# Sheet3_SenseCkts_Programming_Interface.net
KiCad netlist of a schematic drawn in Altium Designer
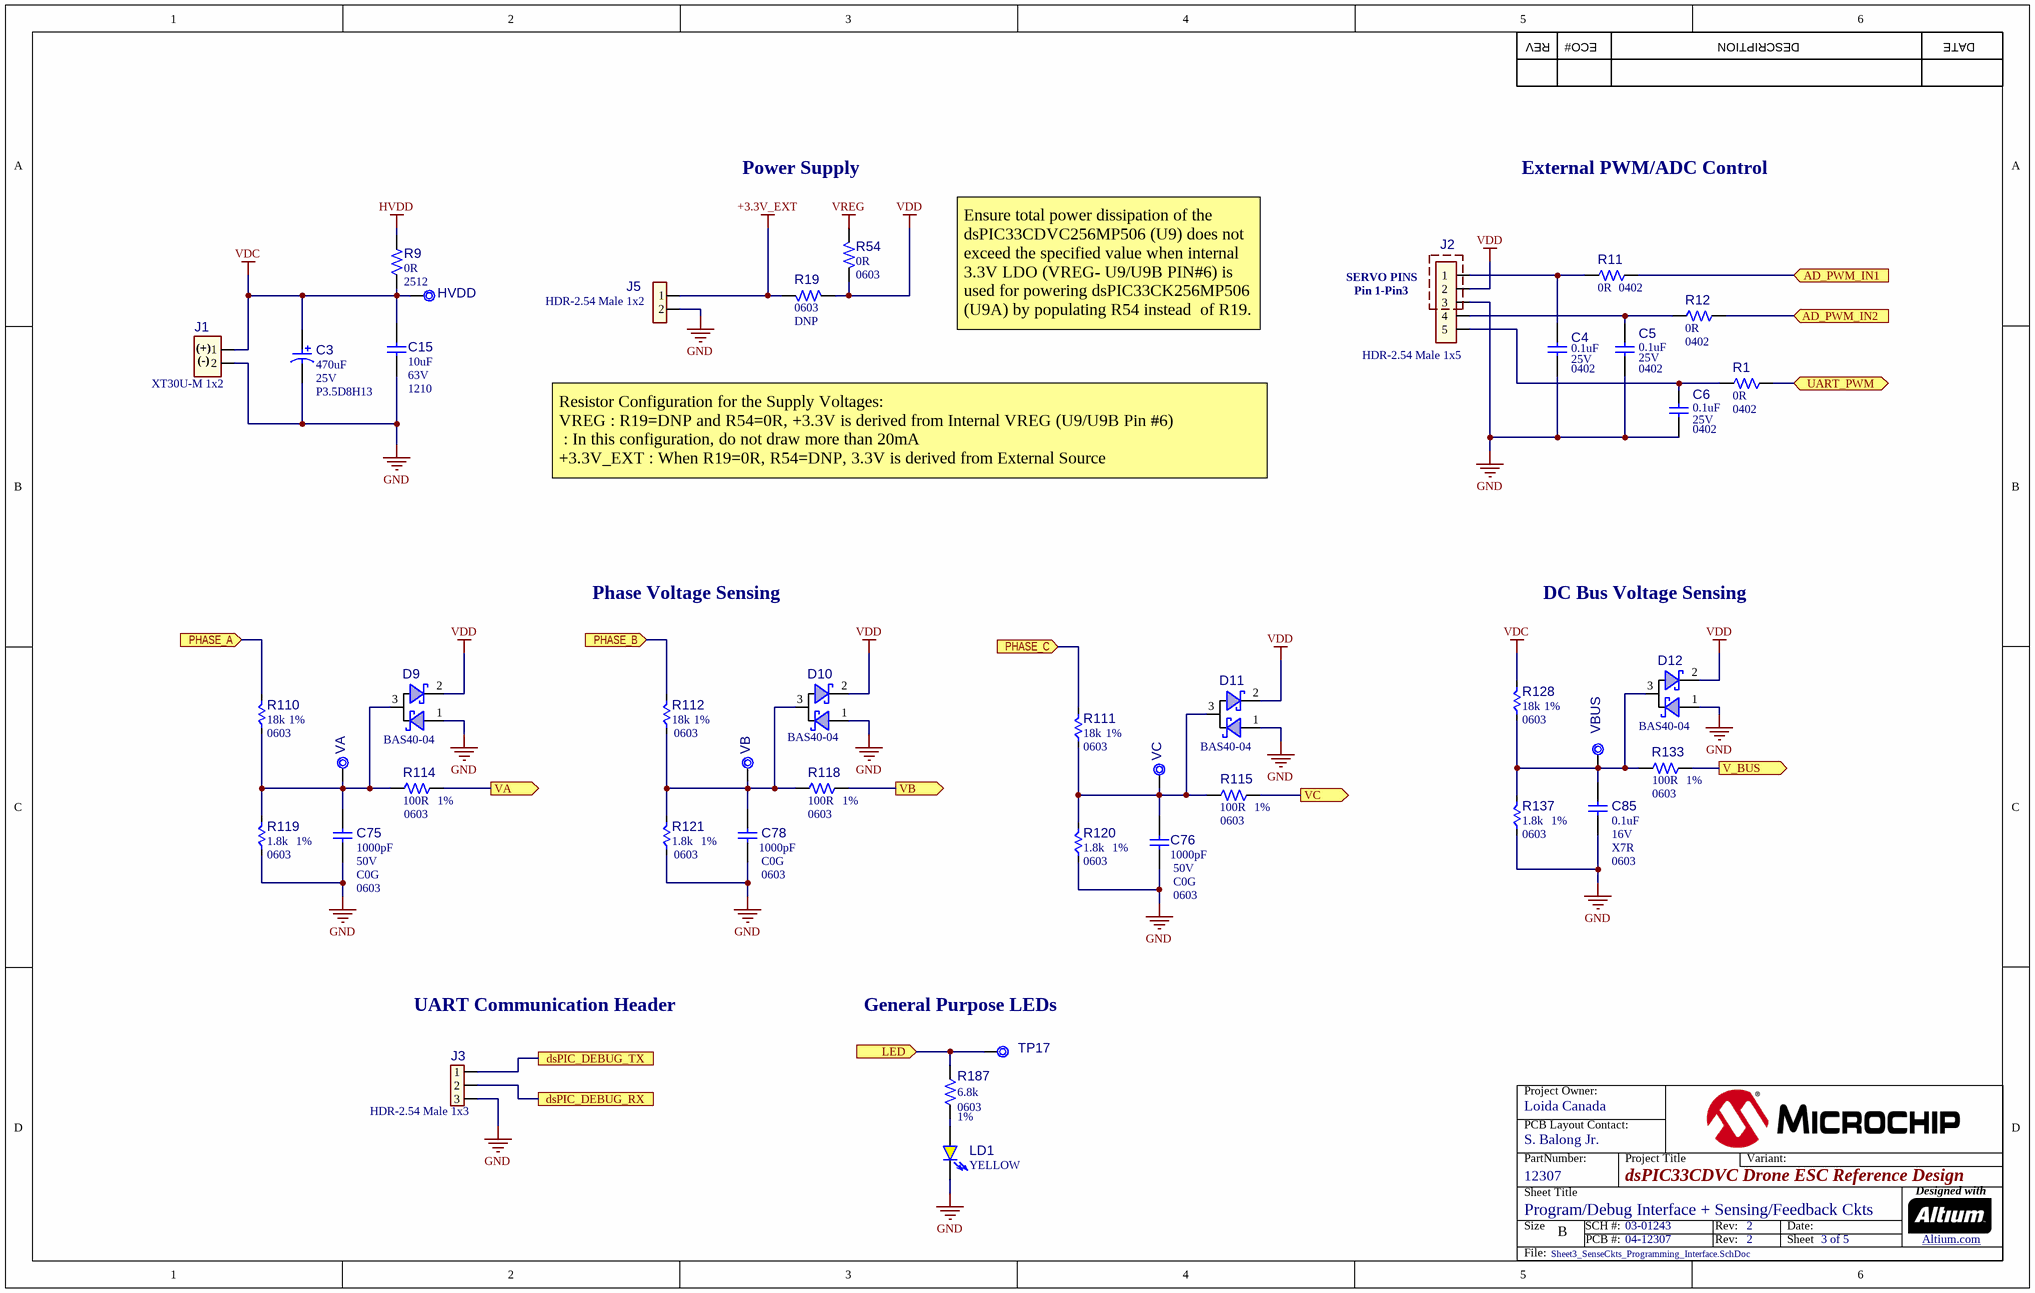
[diagram p0: Sheet3_SenseCkts_Programming_Interface.SchDoc]

(export (version "E")
  (design (tool "Eeschema 10.0.6"))
  (components
    (comp (ref "C3")
      (value "470uF")
      (footprint "CAP_RAD_P3.5D8H13_WE")
      (description "Capacitor")
      (fields
        (field (name "VOLTAGE") "25V")
        (field (name "PACKAGE") "P3.5D8H13")
        (field (name "TOLERANCE") "20%")
        (field (name "Comment") "Capacitor POL")
        (field (name "OWNER") "Severino Balong Jr.")
      )
      (libsource (lib "MCHP-CDB") (part "Capacitor POL"))
    )
    (comp (ref "C4")
      (value "0.1uF")
      (footprint "CAP_C_0402")
      (fields
        (field (name "VOLTAGE") "25V")
        (field (name "PACKAGE") "0402")
        (field (name "TOLERANCE") "10%")
        (field (name "Comment") "Capacitor NP")
        (field (name "OWNER") "Randolph Sobrepena")
      )
      (libsource (lib "") (part "Capacitor NP_1"))
    )
    (comp (ref "C5")
      (value "0.1uF")
      (footprint "CAP_C_0402")
      (fields
        (field (name "VOLTAGE") "25V")
        (field (name "PACKAGE") "0402")
        (field (name "TOLERANCE") "10%")
        (field (name "Comment") "Capacitor NP")
        (field (name "OWNER") "Randolph Sobrepena")
      )
      (libsource (lib "") (part "Capacitor NP_1"))
    )
    (comp (ref "C6")
      (value "0.1uF")
      (footprint "CAP_C_0402")
      (fields
        (field (name "VOLTAGE") "25V")
        (field (name "PACKAGE") "0402")
        (field (name "TOLERANCE") "10%")
        (field (name "Comment") "Capacitor NP")
        (field (name "OWNER") "Randolph Sobrepena")
      )
      (libsource (lib "") (part "Capacitor NP_1"))
    )
    (comp (ref "C15")
      (value "10uF")
      (footprint "CAP_C_1210")
      (fields
        (field (name "VOLTAGE") "63V")
        (field (name "PACKAGE") "1210")
        (field (name "TOLERANCE") "10%")
        (field (name "Comment") "Capacitor NP")
        (field (name "OWNER") "Narasimha Murthy")
      )
      (libsource (lib "") (part "Capacitor NP_1"))
    )
    (comp (ref "C75")
      (value "1000pF")
      (footprint "CAP_C_0603")
      (description "Capacitor")
      (fields
        (field (name "VOLTAGE") "50V")
        (field (name "PACKAGE") "0603")
        (field (name "TOLERANCE") "5%")
        (field (name "TEMPERATURE COEFFCIENT") "C0G")
        (field (name "Comment") "Capacitor NP")
      )
      (libsource (lib "MCHP-CDB") (part "Capacitor NP"))
    )
    (comp (ref "C76")
      (value "1000pF")
      (footprint "CAP_C_0603")
      (description "Capacitor")
      (fields
        (field (name "VOLTAGE") "50V")
        (field (name "PACKAGE") "0603")
        (field (name "TOLERANCE") "5%")
        (field (name "TEMPERATURE COEFFCIENT") "C0G")
        (field (name "Comment") "Capacitor NP")
      )
      (libsource (lib "MCHP-CDB") (part "Capacitor NP"))
    )
    (comp (ref "C78")
      (value "1000pF")
      (footprint "CAP_C_0603")
      (description "Capacitor")
      (fields
        (field (name "VOLTAGE") "50V")
        (field (name "PACKAGE") "0603")
        (field (name "TOLERANCE") "5%")
        (field (name "TEMPERATURE COEFFCIENT") "C0G")
      )
      (libsource (lib "MCHP-CDB") (part "Capacitor NP"))
    )
    (comp (ref "C85")
      (value "0.1uF")
      (footprint "CAP_C_0603")
      (description "Capacitor")
      (fields
        (field (name "VOLTAGE") "16V")
        (field (name "PACKAGE") "0603")
        (field (name "TOLERANCE") "10%")
        (field (name "TEMPERATURE COEFFCIENT") "X7R")
        (field (name "Comment") "Capacitor NP")
        (field (name "OWNER") "Cristian Papuc")
      )
      (libsource (lib "MCHP-CDB") (part "Capacitor NP"))
    )
    (comp (ref "D9")
      (value "BAS40-04")
      (footprint "SOT-23-3")
      (fields
        (field (name "POWER") "200mW")
        (field (name "Comment") "Diode Schottky Dual AK")
        (field (name "OWNER") "Stephen Humberd")
      )
      (libsource (lib "MCHP-CDB") (part "Diode Schottky Dual AK"))
    )
    (comp (ref "D10")
      (value "BAS40-04")
      (footprint "SOT-23-3")
      (fields
        (field (name "POWER") "200mW")
        (field (name "Comment") "Diode Schottky Dual AK")
        (field (name "OWNER") "Stephen Humberd")
      )
      (libsource (lib "MCHP-CDB") (part "Diode Schottky Dual AK"))
    )
    (comp (ref "D11")
      (value "BAS40-04")
      (footprint "SOT-23-3")
      (fields
        (field (name "POWER") "200mW")
        (field (name "Comment") "Diode Schottky Dual AK")
        (field (name "OWNER") "Stephen Humberd")
      )
      (libsource (lib "MCHP-CDB") (part "Diode Schottky Dual AK"))
    )
    (comp (ref "D12")
      (value "BAS40-04")
      (footprint "SOT-23-3")
      (fields
        (field (name "POWER") "200mW")
        (field (name "Comment") "Diode Schottky Dual AK")
        (field (name "OWNER") "Stephen Humberd")
      )
      (libsource (lib "MCHP-CDB") (part "Diode Schottky Dual AK"))
    )
    (comp (ref "HVDD")
      (value "Test Point No BOM")
      (footprint "TP_1.1x0.6")
      (description "Test Point")
      (fields (field (name "OWNER") "Severino Balong Jr."))
      (libsource (lib "MCHP-CDB") (part "Test Point No BOM"))
    )
    (comp (ref "J1")
      (value "XT30U-M 1x2")
      (footprint "CON TERMINAL XT30U-M 5mm 1x2 Male 30A TH V")
      (fields
        (field (name "VOLTAGE") "500V")
        (field (name "Comment") "CON 1x2 POLARIZED")
        (field (name "OWNER") "Octavian Stroe")
      )
      (libsource (lib "MCHP-CDB") (part "CON 1x2 POLARIZED"))
    )
    (comp (ref "J2")
      (value "HDR-2.54 Male 1x5")
      (footprint "HDR_M_2.54_1x5_MH5.84_IH2.54_TH3.2_TH_VERT")
      (fields (field (name "Comment") "Header 1x5") (field (name "OWNER") "Deepak Kariyappa"))
      (libsource (lib "MCHP-CDB") (part "Header 1x5"))
    )
    (comp (ref "J3")
      (value "HDR-2.54 Male 1x3")
      (footprint "HDR_M_2.54_1x3_TH_V_SAM_TSW-103-08-G-S")
      (fields
        (field (name "VOLTAGE") "550VAC")
        (field (name "Comment") "Header 1x3")
        (field (name "OWNER") "Dragos Danaila")
      )
      (libsource (lib "MCHP-CDB") (part "Header 1x3"))
    )
    (comp (ref "J5")
      (value "HDR-2.54 Male 1x2")
      (footprint "HDR_M_2.54_1x2_TH_V_SAM_TSW-102-08-G-S")
      (fields
        (field (name "VOLTAGE") "550VAC")
        (field (name "Comment") "Header 1x2")
        (field (name "OWNER") "Dragos Danaila")
      )
      (libsource (lib "MCHP-CDB") (part "Header 1x2"))
    )
    (comp (ref "LD1")
      (value "YELLOW")
      (footprint "LED_0603_Yellow")
      (description "LED")
      (fields
        (field (name "POWER") "72mW")
        (field (name "Comment") "LED_yellow")
        (field (name "OWNER") "Narasimha Murthy")
      )
      (libsource (lib "MCHP-CDB") (part "LED_yellow"))
    )
    (comp (ref "R1")
      (value "0R")
      (footprint "RES_C_0402")
      (description "Resistor")
      (fields
        (field (name "PACKAGE") "0402")
        (field (name "VOLTAGE") "50V")
        (field (name "POWER") "1/16W")
        (field (name "OWNER") "Balaji Narayana")
      )
      (libsource (lib "MCHP-CDB") (part "Resistor"))
    )
    (comp (ref "R9")
      (value "0R")
      (footprint "RES_C_2512")
      (description "Resistor")
      (fields
        (field (name "PACKAGE") "2512")
        (field (name "VOLTAGE") "500V")
        (field (name "POWER") "1W")
        (field (name "OWNER") "Narasimha Murthy")
      )
      (libsource (lib "") (part "Resistor_1"))
    )
    (comp (ref "R11")
      (value "0R")
      (footprint "RES_C_0402")
      (description "Resistor")
      (fields
        (field (name "PACKAGE") "0402")
        (field (name "VOLTAGE") "50V")
        (field (name "POWER") "1/16W")
        (field (name "OWNER") "Balaji Narayana")
      )
      (libsource (lib "MCHP-CDB") (part "Resistor"))
    )
    (comp (ref "R12")
      (value "0R")
      (footprint "RES_C_0402")
      (description "Resistor")
      (fields
        (field (name "PACKAGE") "0402")
        (field (name "VOLTAGE") "50V")
        (field (name "POWER") "1/16W")
        (field (name "OWNER") "Balaji Narayana")
      )
      (libsource (lib "MCHP-CDB") (part "Resistor"))
    )
    (comp (ref "R19")
      (value "Resistor")
      (footprint "RES_C_0603")
      (fields (field (name "PACKAGE") "0603") (field (name "POWER") "1/10W") (field (name "POPULATED") "DNP"))
      (libsource (lib "MCHP-CDB") (part "Resistor"))
    )
    (comp (ref "R54")
      (value "0R")
      (footprint "RES_C_0603")
      (description "Resistor")
      (fields (field (name "PACKAGE") "0603") (field (name "POWER") "1/10W"))
      (libsource (lib "MCHP-CDB") (part "Resistor"))
    )
    (comp (ref "R110")
      (value "18k")
      (footprint "RES_C_0603")
      (description "Resistor")
      (fields
        (field (name "PACKAGE") "0603")
        (field (name "TOLERANCE") "1%")
        (field (name "VOLTAGE") "75V")
        (field (name "POWER") "1/10W")
        (field (name "OWNER") "Bogdan P (M91398)")
      )
      (libsource (lib "") (part "Resistor_2"))
    )
    (comp (ref "R111")
      (value "18k")
      (footprint "RES_C_0603")
      (description "Resistor")
      (fields
        (field (name "PACKAGE") "0603")
        (field (name "TOLERANCE") "1%")
        (field (name "VOLTAGE") "75V")
        (field (name "POWER") "1/10W")
        (field (name "OWNER") "Bogdan P (M91398)")
      )
      (libsource (lib "") (part "Resistor_2"))
    )
    (comp (ref "R112")
      (value "18k")
      (footprint "RES_C_0603")
      (description "Resistor")
      (fields
        (field (name "PACKAGE") "0603")
        (field (name "TOLERANCE") "1%")
        (field (name "VOLTAGE") "75V")
        (field (name "POWER") "1/10W")
        (field (name "OWNER") "Bogdan P (M91398)")
      )
      (libsource (lib "") (part "Resistor_2"))
    )
    (comp (ref "R114")
      (value "100R")
      (footprint "RES_C_0603")
      (description "Resistor")
      (fields
        (field (name "PACKAGE") "0603")
        (field (name "TOLERANCE") "1%")
        (field (name "VOLTAGE") "75V")
        (field (name "POWER") "1/10W")
      )
      (libsource (lib "") (part "Resistor_1"))
    )
    (comp (ref "R115")
      (value "100R")
      (footprint "RES_C_0603")
      (description "Resistor")
      (fields
        (field (name "PACKAGE") "0603")
        (field (name "TOLERANCE") "1%")
        (field (name "VOLTAGE") "75V")
        (field (name "POWER") "1/10W")
      )
      (libsource (lib "") (part "Resistor_1"))
    )
    (comp (ref "R118")
      (value "100R")
      (footprint "RES_C_0603")
      (description "Resistor")
      (fields
        (field (name "PACKAGE") "0603")
        (field (name "TOLERANCE") "1%")
        (field (name "VOLTAGE") "75V")
        (field (name "POWER") "1/10W")
      )
      (libsource (lib "") (part "Resistor_1"))
    )
    (comp (ref "R119")
      (value "1.8k")
      (footprint "RES_C_0603")
      (description "Resistor")
      (fields
        (field (name "PACKAGE") "0603")
        (field (name "TOLERANCE") "1%")
        (field (name "VOLTAGE") "75V")
        (field (name "POWER") "1/10W")
        (field (name "OWNER") "Bogdan P (M91398)")
      )
      (libsource (lib "") (part "Resistor_2"))
    )
    (comp (ref "R120")
      (value "1.8k")
      (footprint "RES_C_0603")
      (description "Resistor")
      (fields
        (field (name "PACKAGE") "0603")
        (field (name "TOLERANCE") "1%")
        (field (name "VOLTAGE") "75V")
        (field (name "POWER") "1/10W")
        (field (name "OWNER") "Bogdan P (M91398)")
      )
      (libsource (lib "") (part "Resistor_2"))
    )
    (comp (ref "R121")
      (value "1.8k")
      (footprint "RES_C_0603")
      (description "Resistor")
      (fields
        (field (name "PACKAGE") "0603")
        (field (name "TOLERANCE") "1%")
        (field (name "VOLTAGE") "75V")
        (field (name "POWER") "1/10W")
        (field (name "OWNER") "Bogdan P (M91398)")
      )
      (libsource (lib "") (part "Resistor_2"))
    )
    (comp (ref "R128")
      (value "18k")
      (footprint "RES_C_0603")
      (description "Resistor")
      (fields
        (field (name "PACKAGE") "0603")
        (field (name "TOLERANCE") "1%")
        (field (name "VOLTAGE") "75V")
        (field (name "POWER") "1/10W")
        (field (name "OWNER") "Bogdan P (M91398)")
      )
      (libsource (lib "") (part "Resistor_2"))
    )
    (comp (ref "R133")
      (value "100R")
      (footprint "RES_C_0603")
      (description "Resistor")
      (fields
        (field (name "PACKAGE") "0603")
        (field (name "TOLERANCE") "1%")
        (field (name "VOLTAGE") "75V")
        (field (name "POWER") "1/10W")
      )
      (libsource (lib "") (part "Resistor_1"))
    )
    (comp (ref "R137")
      (value "1.8k")
      (footprint "RES_C_0603")
      (description "Resistor")
      (fields
        (field (name "PACKAGE") "0603")
        (field (name "TOLERANCE") "1%")
        (field (name "VOLTAGE") "75V")
        (field (name "POWER") "1/10W")
        (field (name "OWNER") "Bogdan P (M91398)")
      )
      (libsource (lib "") (part "Resistor_2"))
    )
    (comp (ref "R187")
      (value "6.8k")
      (footprint "RES_C_0603")
      (description "Resistor")
      (fields
        (field (name "TOLERANCE") "1%")
        (field (name "PACKAGE") "0603")
        (field (name "POWER") "1/10W")
        (field (name "VOLTAGE") "75V")
      )
      (libsource (lib "MCHP-CDB") (part "Resistor"))
    )
    (comp (ref "TP17")
      (value "Test Point No BOM")
      (footprint "TP_TH_0.7PADX0.4HOLE")
      (description "Test Point")
      (fields (field (name "OWNER") "Severino Balong Jr."))
      (libsource (lib "MCHP-CDB") (part "Test Point No BOM"))
    )
    (comp (ref "VA")
      (value "Test Point No BOM")
      (footprint "TP_TH_0.7PADX0.4HOLE")
      (description "Test Point")
      (fields (field (name "OWNER") "Severino Balong Jr."))
      (libsource (lib "MCHP-CDB") (part "Test Point No BOM"))
    )
    (comp (ref "VB")
      (value "Test Point No BOM")
      (footprint "TP_TH_0.7PADX0.4HOLE")
      (description "Test Point")
      (fields (field (name "OWNER") "Severino Balong Jr."))
      (libsource (lib "MCHP-CDB") (part "Test Point No BOM"))
    )
    (comp (ref "VBUS")
      (value "Test Point No BOM")
      (footprint "TP_TH_0.7PADX0.4HOLE")
      (description "Test Point")
      (fields (field (name "OWNER") "Severino Balong Jr."))
      (libsource (lib "MCHP-CDB") (part "Test Point No BOM"))
    )
    (comp (ref "VC")
      (value "Test Point No BOM")
      (footprint "TP_TH_0.7PADX0.4HOLE")
      (description "Test Point")
      (fields (field (name "OWNER") "Severino Balong Jr."))
      (libsource (lib "MCHP-CDB") (part "Test Point No BOM"))
    )
  )
  (nets
    (net (code "1") (name "+3.3V_EXT") (class "Default")
      (node (ref "J5") (pin "1") (pinfunction "1_1") (pintype "passive"))
      (node (ref "R19") (pin "2") (pinfunction "2_2") (pintype "passive"))
    )
    (net (code "2") (name "/AD_PWM_IN1") (class "Default")
      (node (ref "R11") (pin "2") (pinfunction "2_2") (pintype "passive"))
    )
    (net (code "3") (name "/AD_PWM_IN2") (class "Default")
      (node (ref "R12") (pin "2") (pinfunction "2_2") (pintype "passive"))
    )
    (net (code "4") (name "/LED") (class "Default")
      (node (ref "R187") (pin "1") (pinfunction "1_1") (pintype "passive"))
      (node (ref "TP17") (pin "1") (pinfunction "1_1") (pintype "passive"))
    )
    (net (code "5") (name "/PHASE_A") (class "Default")
      (node (ref "R110") (pin "1") (pinfunction "1_1") (pintype "passive"))
    )
    (net (code "6") (name "/PHASE_B") (class "Default")
      (node (ref "R112") (pin "1") (pinfunction "1_1") (pintype "passive"))
    )
    (net (code "7") (name "/PHASE_C") (class "Default")
      (node (ref "R111") (pin "1") (pinfunction "1_1") (pintype "passive"))
    )
    (net (code "8") (name "/UART_PWM") (class "Default")
      (node (ref "R1") (pin "2") (pinfunction "2_2") (pintype "passive"))
    )
    (net (code "9") (name "/VA") (class "Default")
      (node (ref "R114") (pin "2") (pinfunction "2_2") (pintype "passive"))
    )
    (net (code "10") (name "/VB") (class "Default")
      (node (ref "R118") (pin "2") (pinfunction "2_2") (pintype "passive"))
    )
    (net (code "11") (name "/VC") (class "Default")
      (node (ref "R115") (pin "2") (pinfunction "2_2") (pintype "passive"))
    )
    (net (code "12") (name "/V_BUS") (class "Default")
      (node (ref "R133") (pin "2") (pinfunction "2_2") (pintype "passive"))
    )
    (net (code "13") (name "/dsPIC_DEBUG_RX") (class "Default")
      (node (ref "J3") (pin "2") (pinfunction "2_2") (pintype "passive"))
    )
    (net (code "14") (name "/dsPIC_DEBUG_TX") (class "Default")
      (node (ref "J3") (pin "1") (pinfunction "1_1") (pintype "passive"))
    )
    (net (code "15") (name "GND") (class "Default")
      (node (ref "C15") (pin "1") (pinfunction "1_1") (pintype "passive"))
      (node (ref "C3") (pin "2") (pinfunction "2_2") (pintype "passive"))
      (node (ref "C4") (pin "1") (pinfunction "1_1") (pintype "passive"))
      (node (ref "C5") (pin "1") (pinfunction "1_1") (pintype "passive"))
      (node (ref "C6") (pin "1") (pinfunction "1_1") (pintype "passive"))
      (node (ref "C75") (pin "1") (pinfunction "1_1") (pintype "passive"))
      (node (ref "C76") (pin "1") (pinfunction "1_1") (pintype "passive"))
      (node (ref "C78") (pin "1") (pinfunction "1_1") (pintype "passive"))
      (node (ref "C85") (pin "1") (pinfunction "1_1") (pintype "passive"))
      (node (ref "D10") (pin "1") (pinfunction "A_1") (pintype "passive"))
      (node (ref "D11") (pin "1") (pinfunction "A_1") (pintype "passive"))
      (node (ref "D12") (pin "1") (pinfunction "A_1") (pintype "passive"))
      (node (ref "D9") (pin "1") (pinfunction "A_1") (pintype "passive"))
      (node (ref "J1") (pin "2") (pinfunction "2_2") (pintype "passive"))
      (node (ref "J2") (pin "3") (pinfunction "3_3") (pintype "passive"))
      (node (ref "J3") (pin "3") (pinfunction "3_3") (pintype "passive"))
      (node (ref "J5") (pin "2") (pinfunction "2_2") (pintype "passive"))
      (node (ref "LD1") (pin "2") (pinfunction "K_2") (pintype "passive"))
      (node (ref "R119") (pin "2") (pinfunction "2_2") (pintype "passive"))
      (node (ref "R120") (pin "2") (pinfunction "2_2") (pintype "passive"))
      (node (ref "R121") (pin "2") (pinfunction "2_2") (pintype "passive"))
      (node (ref "R137") (pin "2") (pinfunction "2_2") (pintype "passive"))
    )
    (net (code "16") (name "HVDD") (class "Default")
      (node (ref "R9") (pin "2") (pinfunction "2_2") (pintype "passive"))
    )
    (net (code "17") (name "Net-(C4-Pad2)") (class "Default")
      (node (ref "C4") (pin "2") (pinfunction "2_2") (pintype "passive"))
      (node (ref "J2") (pin "1") (pinfunction "1_1") (pintype "passive"))
      (node (ref "R11") (pin "1") (pinfunction "1_1") (pintype "passive"))
    )
    (net (code "18") (name "Net-(C5-Pad2)") (class "Default")
      (node (ref "C5") (pin "2") (pinfunction "2_2") (pintype "passive"))
      (node (ref "J2") (pin "4") (pinfunction "4_4") (pintype "passive"))
      (node (ref "R12") (pin "1") (pinfunction "1_1") (pintype "passive"))
    )
    (net (code "19") (name "Net-(C6-Pad2)") (class "Default")
      (node (ref "C6") (pin "2") (pinfunction "2_2") (pintype "passive"))
      (node (ref "J2") (pin "5") (pinfunction "5_5") (pintype "passive"))
      (node (ref "R1") (pin "1") (pinfunction "1_1") (pintype "passive"))
    )
    (net (code "20") (name "Net-(D9-KA)") (class "Default")
      (node (ref "C75") (pin "2") (pinfunction "2_2") (pintype "passive"))
      (node (ref "D9") (pin "3") (pinfunction "KA_3") (pintype "passive"))
      (node (ref "R110") (pin "2") (pinfunction "2_2") (pintype "passive"))
      (node (ref "R114") (pin "1") (pinfunction "1_1") (pintype "passive"))
      (node (ref "R119") (pin "1") (pinfunction "1_1") (pintype "passive"))
      (node (ref "VA") (pin "1") (pinfunction "1_1") (pintype "passive"))
    )
    (net (code "21") (name "Net-(D10-KA)") (class "Default")
      (node (ref "C78") (pin "2") (pinfunction "2_2") (pintype "passive"))
      (node (ref "D10") (pin "3") (pinfunction "KA_3") (pintype "passive"))
      (node (ref "R112") (pin "2") (pinfunction "2_2") (pintype "passive"))
      (node (ref "R118") (pin "1") (pinfunction "1_1") (pintype "passive"))
      (node (ref "R121") (pin "1") (pinfunction "1_1") (pintype "passive"))
      (node (ref "VB") (pin "1") (pinfunction "1_1") (pintype "passive"))
    )
    (net (code "22") (name "Net-(D11-KA)") (class "Default")
      (node (ref "C76") (pin "2") (pinfunction "2_2") (pintype "passive"))
      (node (ref "D11") (pin "3") (pinfunction "KA_3") (pintype "passive"))
      (node (ref "R111") (pin "2") (pinfunction "2_2") (pintype "passive"))
      (node (ref "R115") (pin "1") (pinfunction "1_1") (pintype "passive"))
      (node (ref "R120") (pin "1") (pinfunction "1_1") (pintype "passive"))
      (node (ref "VC") (pin "1") (pinfunction "1_1") (pintype "passive"))
    )
    (net (code "23") (name "Net-(D12-KA)") (class "Default")
      (node (ref "C85") (pin "2") (pinfunction "2_2") (pintype "passive"))
      (node (ref "D12") (pin "3") (pinfunction "KA_3") (pintype "passive"))
      (node (ref "R128") (pin "2") (pinfunction "2_2") (pintype "passive"))
      (node (ref "R133") (pin "1") (pinfunction "1_1") (pintype "passive"))
      (node (ref "R137") (pin "1") (pinfunction "1_1") (pintype "passive"))
      (node (ref "VBUS") (pin "1") (pinfunction "1_1") (pintype "passive"))
    )
    (net (code "24") (name "Net-(LD1-A)") (class "Default")
      (node (ref "LD1") (pin "1") (pinfunction "A_1") (pintype "passive"))
      (node (ref "R187") (pin "2") (pinfunction "2_2") (pintype "passive"))
    )
    (net (code "25") (name "VDC") (class "Default")
      (node (ref "C15") (pin "2") (pinfunction "2_2") (pintype "passive"))
      (node (ref "C3") (pin "1") (pinfunction "1_1") (pintype "passive"))
      (node (ref "HVDD") (pin "1") (pinfunction "1_1") (pintype "passive"))
      (node (ref "J1") (pin "1") (pinfunction "1_1") (pintype "passive"))
      (node (ref "R128") (pin "1") (pinfunction "1_1") (pintype "passive"))
      (node (ref "R9") (pin "1") (pinfunction "1_1") (pintype "passive"))
    )
    (net (code "26") (name "VDD") (class "Default")
      (node (ref "D10") (pin "2") (pinfunction "K_2") (pintype "passive"))
      (node (ref "D11") (pin "2") (pinfunction "K_2") (pintype "passive"))
      (node (ref "D12") (pin "2") (pinfunction "K_2") (pintype "passive"))
      (node (ref "D9") (pin "2") (pinfunction "K_2") (pintype "passive"))
      (node (ref "J2") (pin "2") (pinfunction "2_2") (pintype "passive"))
      (node (ref "R19") (pin "1") (pinfunction "1_1") (pintype "passive"))
      (node (ref "R54") (pin "2") (pinfunction "2_2") (pintype "passive"))
    )
    (net (code "27") (name "VREG") (class "Default")
      (node (ref "R54") (pin "1") (pinfunction "1_1") (pintype "passive"))
    )
  )
)
